# driver-power-stage.net
KiCad netlist of a schematic drawn in Altium Designer
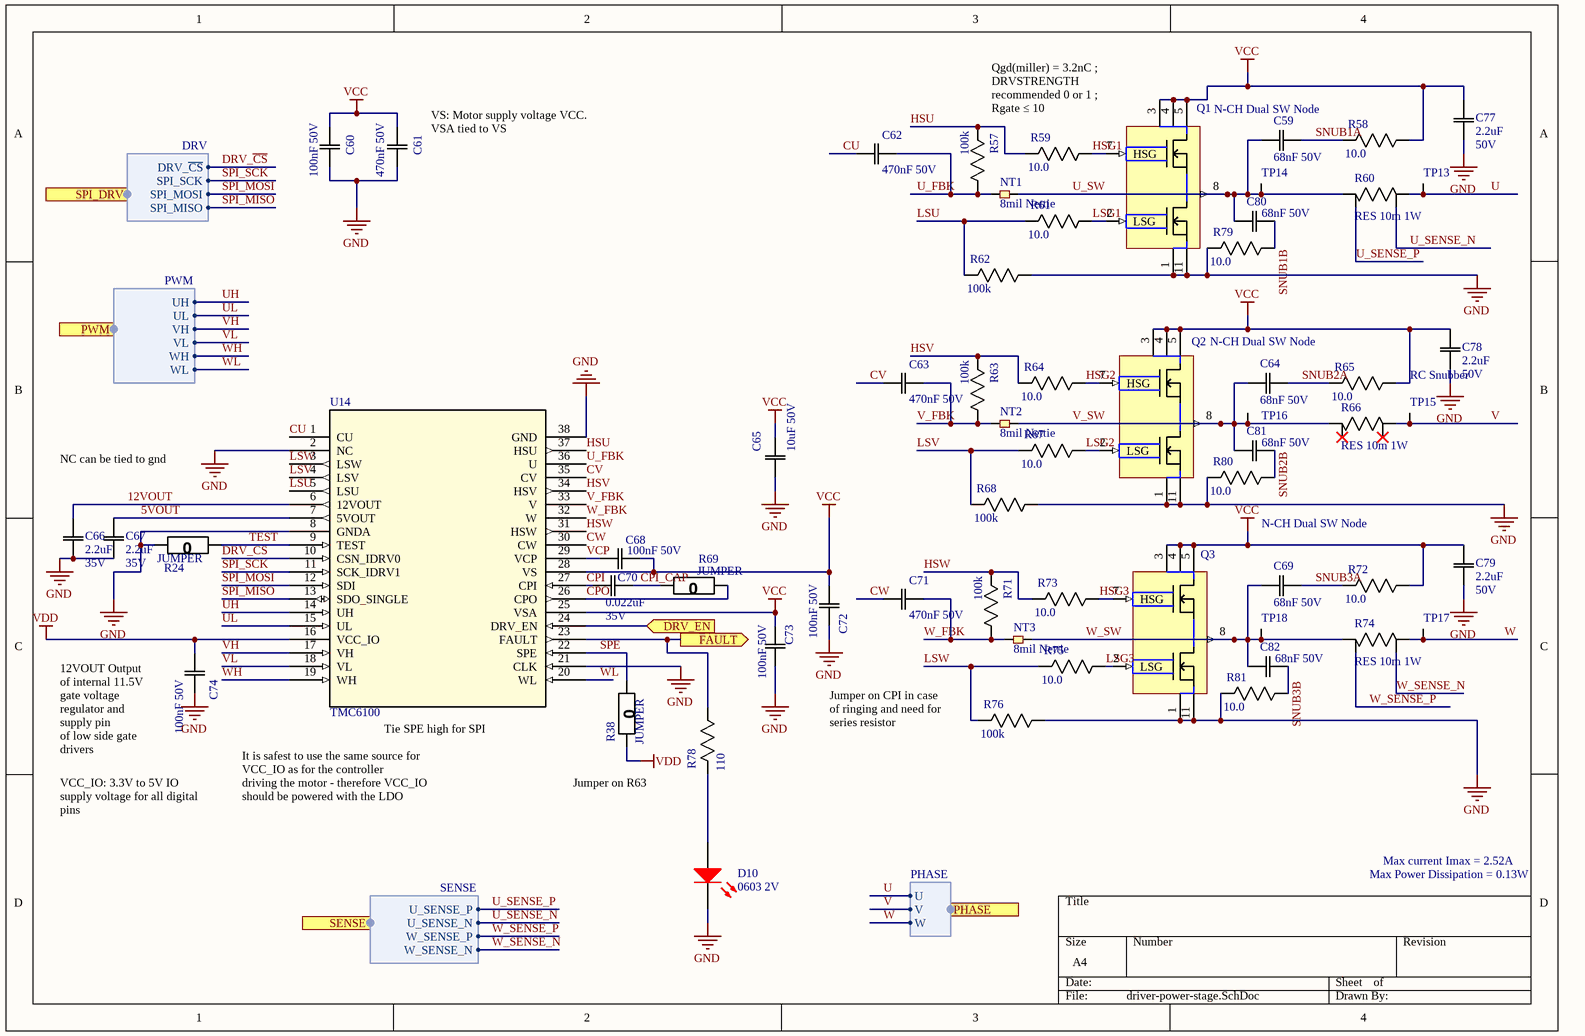
[diagram p0: driver-power-stage.SchDoc]

(export (version "E")
  (design (tool "Eeschema 10.0.6"))
  (components
    (comp (ref "C59")
      (value "68nF 50V")
      (footprint "0603")
      (description "Default Symbol for Capacitors")
      (fields (field (name "PART NUMBER") "CAP 0.068uF 50V") (field (name "TOLERANCE") "10%"))
      (libsource (lib "capacitor_library") (part "CAP_Default"))
    )
    (comp (ref "C60")
      (value "100nF 50V")
      (footprint "0603")
      (description "Default Symbol for Capacitors")
      (fields (field (name "TOLERANCE") "10%") (field (name "PART NUMBER") "CAP 100nF 50V"))
      (libsource (lib "capacitor_library") (part "CAP_Default"))
    )
    (comp (ref "C61")
      (value "470nF 50V")
      (footprint "0603")
      (description "Default Symbol for Capacitors")
      (fields (field (name "TOLERANCE") "10%") (field (name "PART NUMBER") "CAP 470nF 50V"))
      (libsource (lib "capacitor_library") (part "CAP_Default"))
    )
    (comp (ref "C62")
      (value "470nF 50V")
      (footprint "0603")
      (description "Default Symbol for Capacitors")
      (fields (field (name "TOLERANCE") "10%") (field (name "PART NUMBER") "CAP 470nF 50V"))
      (libsource (lib "capacitor_library") (part "CAP_Default"))
    )
    (comp (ref "C63")
      (value "470nF 50V")
      (footprint "0603")
      (description "Default Symbol for Capacitors")
      (fields (field (name "TOLERANCE") "10%") (field (name "PART NUMBER") "CAP 470nF 50V"))
      (libsource (lib "capacitor_library") (part "CAP_Default"))
    )
    (comp (ref "C64")
      (value "68nF 50V")
      (footprint "0603")
      (description "Default Symbol for Capacitors")
      (fields (field (name "PART NUMBER") "CAP 0.068uF 50V") (field (name "TOLERANCE") "10%"))
      (libsource (lib "capacitor_library") (part "CAP_Default"))
    )
    (comp (ref "C65")
      (value "10uF 50V")
      (footprint "0805")
      (description "Default Symbol for Capacitors")
      (fields (field (name "TOLERANCE") "10%") (field (name "PART NUMBER") "CAP 10uF 50V"))
      (libsource (lib "capacitor_library") (part "CAP_Default"))
    )
    (comp (ref "C66")
      (value "2.2uF")
      (footprint "0603")
      (description "Default Symbol for Capacitors")
      (fields
        (field (name "TOLERANCE") "10%")
        (field (name "RATING") "35V")
        (field (name "PART NUMBER") "CAP 2.2uF 35V")
      )
      (libsource (lib "capacitor_library") (part "CAP_Default"))
    )
    (comp (ref "C67")
      (value "2.2uF")
      (footprint "0603")
      (description "Default Symbol for Capacitors")
      (fields
        (field (name "TOLERANCE") "10%")
        (field (name "RATING") "35V")
        (field (name "PART NUMBER") "CAP 2.2uF 35V")
      )
      (libsource (lib "capacitor_library") (part "CAP_Default"))
    )
    (comp (ref "C68")
      (value "100nF 50V")
      (footprint "0603")
      (description "Default Symbol for Capacitors")
      (fields (field (name "TOLERANCE") "10%") (field (name "PART NUMBER") "CAP 100nF 50V"))
      (libsource (lib "capacitor_library") (part "CAP_Default"))
    )
    (comp (ref "C69")
      (value "68nF 50V")
      (footprint "0603")
      (description "Default Symbol for Capacitors")
      (fields (field (name "PART NUMBER") "CAP 0.068uF 50V") (field (name "TOLERANCE") "10%"))
      (libsource (lib "capacitor_library") (part "CAP_Default"))
    )
    (comp (ref "C70")
      (value "0.022uF")
      (footprint "0603")
      (description "Default Symbol for Capacitors")
      (fields
        (field (name "TOLERANCE") "10%")
        (field (name "RATING") "35V")
        (field (name "PART NUMBER") "CAP 0.022uF 35V")
      )
      (libsource (lib "capacitor_library") (part "CAP_Default"))
    )
    (comp (ref "C71")
      (value "470nF 50V")
      (footprint "0603")
      (description "Default Symbol for Capacitors")
      (fields (field (name "TOLERANCE") "10%") (field (name "PART NUMBER") "CAP 470nF 50V"))
      (libsource (lib "capacitor_library") (part "CAP_Default"))
    )
    (comp (ref "C72")
      (value "100nF 50V")
      (footprint "0603")
      (description "Default Symbol for Capacitors")
      (fields (field (name "TOLERANCE") "10%") (field (name "PART NUMBER") "CAP 100nF 50V"))
      (libsource (lib "capacitor_library") (part "CAP_Default"))
    )
    (comp (ref "C73")
      (value "100nF 50V")
      (footprint "0603")
      (description "Default Symbol for Capacitors")
      (fields (field (name "TOLERANCE") "10%") (field (name "PART NUMBER") "CAP 100nF 50V"))
      (libsource (lib "capacitor_library") (part "CAP_Default"))
    )
    (comp (ref "C74")
      (value "100nF 50V")
      (footprint "0603")
      (description "Default Symbol for Capacitors")
      (fields (field (name "TOLERANCE") "10%") (field (name "PART NUMBER") "CAP 100nF 50V"))
      (libsource (lib "capacitor_library") (part "CAP_Default"))
    )
    (comp (ref "C77")
      (value "2.2uF")
      (footprint "0603")
      (description "CAP CER 2.2UF 50V X5R 0603/0805")
      (fields
        (field (name "TOLERANCE") "10%")
        (field (name "RATING") "50V")
        (field (name "PART NUMBER") "CAP 2.2uF 50V")
      )
      (libsource (lib "capacitor_library") (part "CAP 2.2uF 50V"))
    )
    (comp (ref "C78")
      (value "2.2uF")
      (footprint "0603")
      (description "CAP CER 2.2UF 50V X5R 0603/0805")
      (fields
        (field (name "TOLERANCE") "10%")
        (field (name "RATING") "50V")
        (field (name "PART NUMBER") "CAP 2.2uF 50V")
      )
      (libsource (lib "capacitor_library") (part "CAP 2.2uF 50V"))
    )
    (comp (ref "C79")
      (value "2.2uF")
      (footprint "0603")
      (description "CAP CER 2.2UF 50V X5R 0603/0805")
      (fields
        (field (name "TOLERANCE") "10%")
        (field (name "RATING") "50V")
        (field (name "PART NUMBER") "CAP 2.2uF 50V")
      )
      (libsource (lib "capacitor_library") (part "CAP 2.2uF 50V"))
    )
    (comp (ref "C80")
      (value "68nF 50V")
      (footprint "0603")
      (description "Default Symbol for Capacitors")
      (fields (field (name "PART NUMBER") "CAP 0.068uF 50V") (field (name "TOLERANCE") "10%"))
      (libsource (lib "capacitor_library") (part "CAP_Default"))
    )
    (comp (ref "C81")
      (value "68nF 50V")
      (footprint "0603")
      (description "Default Symbol for Capacitors")
      (fields (field (name "PART NUMBER") "CAP 0.068uF 50V") (field (name "TOLERANCE") "10%"))
      (libsource (lib "capacitor_library") (part "CAP_Default"))
    )
    (comp (ref "C82")
      (value "68nF 50V")
      (footprint "0603")
      (description "Default Symbol for Capacitors")
      (fields (field (name "PART NUMBER") "CAP 0.068uF 50V") (field (name "TOLERANCE") "10%"))
      (libsource (lib "capacitor_library") (part "CAP_Default"))
    )
    (comp (ref "D10")
      (value "0603 2V")
      (footprint "0603 - LED2")
      (description "0603 red led alingap 631nm-639nm water clear 18-180mcd 130d")
      (fields (field (name "PART NUMBER") "LED RED SMD 0603"))
      (libsource (lib "Diode_Library") (part "LED RED SMD 0603"))
    )
    (comp (ref "NT1")
      (value "8mil Nettie")
      (footprint "NT_8mil")
      (description "8mil wide nettie")
      (fields (field (name "PART NUMBER") "NT_8"))
      (libsource (lib "Resistor_Library") (part "NT_8"))
    )
    (comp (ref "NT2")
      (value "8mil Nettie")
      (footprint "NT_8mil")
      (description "8mil wide nettie")
      (fields (field (name "PART NUMBER") "NT_8"))
      (libsource (lib "Resistor_Library") (part "NT_8"))
    )
    (comp (ref "NT3")
      (value "8mil Nettie")
      (footprint "NT_8mil")
      (description "8mil wide nettie")
      (fields (field (name "PART NUMBER") "NT_8"))
      (libsource (lib "Resistor_Library") (part "NT_8"))
    )
    (comp (ref "Q1")
      (value "N-CH Dual SW Node")
      (footprint "12-PowerWQFN")
      (description "MOSFET N+N COMMON PHASE SW 40V 60A")
      (fields (field (name "PART NUMBER") "MOSFET N-CH DUAL NTTFD4D0N04HLTWG"))
      (libsource (lib "Transistor_Library") (part "MOSFET N-CH DUAL NTTFD4D0N04HLTWG"))
    )
    (comp (ref "Q2")
      (value "N-CH Dual SW Node")
      (footprint "12-PowerWQFN")
      (description "MOSFET N+N COMMON PHASE SW 40V 60A")
      (fields (field (name "PART NUMBER") "MOSFET N-CH DUAL NTTFD4D0N04HLTWG"))
      (libsource (lib "Transistor_Library") (part "MOSFET N-CH DUAL NTTFD4D0N04HLTWG"))
    )
    (comp (ref "Q3")
      (value "N-CH Dual SW Node")
      (footprint "12-PowerWQFN")
      (description "MOSFET N+N COMMON PHASE SW 40V 60A")
      (fields (field (name "PART NUMBER") "MOSFET N-CH DUAL NTTFD4D0N04HLTWG"))
      (libsource (lib "Transistor_Library") (part "MOSFET N-CH DUAL NTTFD4D0N04HLTWG"))
    )
    (comp (ref "R24")
      (value "JUMPER")
      (footprint "0603")
      (description "RES SMD 0 OHM JUMPER GENERIC 0805")
      (fields (field (name "PART NUMBER") "RES 0 JUMPER"))
      (libsource (lib "Resistor_Library") (part "RES 0 JUMPER"))
    )
    (comp (ref "R38")
      (value "JUMPER")
      (footprint "0603")
      (description "RES SMD 0 OHM JUMPER GENERIC 0805")
      (fields (field (name "PART NUMBER") "RES 0 JUMPER"))
      (libsource (lib "Resistor_Library") (part "RES 0 JUMPER"))
    )
    (comp (ref "R57")
      (value "100k")
      (footprint "0603")
      (description "RES SMD 100K OHM 5% 1/8W 0805")
      (fields (field (name "TOLERANCE") "5%") (field (name "PART NUMBER") "RES 100k 1/8W 5%"))
      (libsource (lib "Resistor_Library") (part "RES_DEFAULT"))
    )
    (comp (ref "R58")
      (value "10.0")
      (footprint "0603")
      (description "Default Resistor Symbol")
      (fields (field (name "TOLERANCE") "1%") (field (name "PART NUMBER") "RES 10.0 1/8W - 1%"))
      (libsource (lib "") (part "RES_DEFAULT_1"))
    )
    (comp (ref "R59")
      (value "10.0")
      (footprint "0603")
      (description "Default Resistor Symbol")
      (fields (field (name "TOLERANCE") "1%") (field (name "PART NUMBER") "RES 10.0 1/8W - 1%"))
      (libsource (lib "Resistor_Library") (part "RES_DEFAULT"))
    )
    (comp (ref "R60")
      (value "RES 10m 1W")
      (footprint "1206 - Current Sense")
      (description "RES SMD 0.01 OHM 1% 1W 1206")
      (fields (field (name "TOLERANCE") "1%"))
      (libsource (lib "Resistor_Library") (part "RES 10m 1W"))
    )
    (comp (ref "R61")
      (value "10.0")
      (footprint "0603")
      (description "Default Resistor Symbol")
      (fields (field (name "TOLERANCE") "1%") (field (name "PART NUMBER") "RES 10.0 1/8W - 1%"))
      (libsource (lib "Resistor_Library") (part "RES_DEFAULT"))
    )
    (comp (ref "R62")
      (value "100k")
      (footprint "0603")
      (description "RES SMD 100K OHM 5% 1/8W 0805")
      (fields (field (name "TOLERANCE") "5%") (field (name "PART NUMBER") "RES 100k 1/8W 5%"))
      (libsource (lib "Resistor_Library") (part "RES_DEFAULT"))
    )
    (comp (ref "R63")
      (value "100k")
      (footprint "0603")
      (description "RES SMD 100K OHM 5% 1/8W 0805")
      (fields (field (name "TOLERANCE") "5%") (field (name "PART NUMBER") "RES 100k 1/8W 5%"))
      (libsource (lib "Resistor_Library") (part "RES_DEFAULT"))
    )
    (comp (ref "R64")
      (value "10.0")
      (footprint "0603")
      (description "Default Resistor Symbol")
      (fields (field (name "TOLERANCE") "1%") (field (name "PART NUMBER") "RES 10.0 1/8W - 1%"))
      (libsource (lib "") (part "RES_DEFAULT_1"))
    )
    (comp (ref "R65")
      (value "10.0")
      (footprint "0603")
      (description "Default Resistor Symbol")
      (fields (field (name "TOLERANCE") "1%") (field (name "PART NUMBER") "RES 10.0 1/8W - 1%"))
      (libsource (lib "") (part "RES_DEFAULT_1"))
    )
    (comp (ref "R66")
      (value "RES 10m 1W")
      (footprint "1206 - Current Sense")
      (description "RES SMD 0.01 OHM 1% 1W 1206")
      (fields (field (name "TOLERANCE") "1%"))
      (libsource (lib "Resistor_Library") (part "RES 10m 1W"))
    )
    (comp (ref "R67")
      (value "10.0")
      (footprint "0603")
      (description "Default Resistor Symbol")
      (fields (field (name "TOLERANCE") "1%") (field (name "PART NUMBER") "RES 10.0 1/8W - 1%"))
      (libsource (lib "Resistor_Library") (part "RES_DEFAULT"))
    )
    (comp (ref "R68")
      (value "100k")
      (footprint "0603")
      (description "RES SMD 100K OHM 5% 1/8W 0805")
      (fields (field (name "TOLERANCE") "5%") (field (name "PART NUMBER") "RES 100k 1/8W 5%"))
      (libsource (lib "Resistor_Library") (part "RES_DEFAULT"))
    )
    (comp (ref "R69")
      (value "JUMPER")
      (footprint "0603")
      (description "RES SMD 0 OHM JUMPER GENERIC 0805")
      (fields (field (name "PART NUMBER") "RES 0 JUMPER"))
      (libsource (lib "Resistor_Library") (part "RES 0 JUMPER"))
    )
    (comp (ref "R71")
      (value "100k")
      (footprint "0603")
      (description "RES SMD 100K OHM 5% 1/8W 0805")
      (fields (field (name "TOLERANCE") "5%") (field (name "PART NUMBER") "RES 100k 1/8W 5%"))
      (libsource (lib "Resistor_Library") (part "RES_DEFAULT"))
    )
    (comp (ref "R72")
      (value "10.0")
      (footprint "0603")
      (description "Default Resistor Symbol")
      (fields (field (name "TOLERANCE") "1%") (field (name "PART NUMBER") "RES 10.0 1/8W - 1%"))
      (libsource (lib "") (part "RES_DEFAULT_1"))
    )
    (comp (ref "R73")
      (value "10.0")
      (footprint "0603")
      (description "Default Resistor Symbol")
      (fields (field (name "TOLERANCE") "1%") (field (name "PART NUMBER") "RES 10.0 1/8W - 1%"))
      (libsource (lib "") (part "RES_DEFAULT_1"))
    )
    (comp (ref "R74")
      (value "RES 10m 1W")
      (footprint "1206 - Current Sense")
      (description "RES SMD 0.01 OHM 1% 1W 1206")
      (fields (field (name "TOLERANCE") "1%"))
      (libsource (lib "Resistor_Library") (part "RES 10m 1W"))
    )
    (comp (ref "R75")
      (value "10.0")
      (footprint "0603")
      (description "Default Resistor Symbol")
      (fields (field (name "TOLERANCE") "1%") (field (name "PART NUMBER") "RES 10.0 1/8W - 1%"))
      (libsource (lib "") (part "RES_DEFAULT_1"))
    )
    (comp (ref "R76")
      (value "100k")
      (footprint "0603")
      (description "RES SMD 100K OHM 5% 1/8W 0805")
      (fields (field (name "TOLERANCE") "5%") (field (name "PART NUMBER") "RES 100k 1/8W 5%"))
      (libsource (lib "Resistor_Library") (part "RES_DEFAULT"))
    )
    (comp (ref "R78")
      (value "110")
      (footprint "0603")
      (description "Default Resistor Symbol")
      (fields (field (name "TOLERANCE") "1%") (field (name "PART NUMBER") "RES 110.0 1/8W - 1%"))
      (libsource (lib "Resistor_Library") (part "RES_DEFAULT"))
    )
    (comp (ref "R79")
      (value "10.0")
      (footprint "0603")
      (description "Default Resistor Symbol")
      (fields (field (name "TOLERANCE") "1%") (field (name "PART NUMBER") "RES 10.0 1/8W - 1%"))
      (libsource (lib "Resistor_Library") (part "RES_DEFAULT"))
    )
    (comp (ref "R80")
      (value "10.0")
      (footprint "0603")
      (description "Default Resistor Symbol")
      (fields (field (name "TOLERANCE") "1%") (field (name "PART NUMBER") "RES 10.0 1/8W - 1%"))
      (libsource (lib "Resistor_Library") (part "RES_DEFAULT"))
    )
    (comp (ref "R81")
      (value "10.0")
      (footprint "0603")
      (description "Default Resistor Symbol")
      (fields (field (name "TOLERANCE") "1%") (field (name "PART NUMBER") "RES 10.0 1/8W - 1%"))
      (libsource (lib "Resistor_Library") (part "RES_DEFAULT"))
    )
    (comp (ref "TP13")
      (value "U_SL")
      (footprint "TP")
      (fields (field (name "PART NUMBER") "Test Point (Via)"))
      (libsource (lib "IC_Library") (part "Test Point (Via)"))
    )
    (comp (ref "TP14")
      (value "U_SH")
      (footprint "TP")
      (fields (field (name "PART NUMBER") "Test Point (Via)"))
      (libsource (lib "IC_Library") (part "Test Point (Via)"))
    )
    (comp (ref "TP15")
      (value "V_SL")
      (footprint "TP")
      (fields (field (name "PART NUMBER") "Test Point (Via)"))
      (libsource (lib "IC_Library") (part "Test Point (Via)"))
    )
    (comp (ref "TP16")
      (value "V_SH")
      (footprint "TP")
      (fields (field (name "PART NUMBER") "Test Point (Via)"))
      (libsource (lib "IC_Library") (part "Test Point (Via)"))
    )
    (comp (ref "TP17")
      (value "W_SL")
      (footprint "TP")
      (fields (field (name "PART NUMBER") "Test Point (Via)"))
      (libsource (lib "IC_Library") (part "Test Point (Via)"))
    )
    (comp (ref "TP18")
      (value "W_SH")
      (footprint "TP")
      (fields (field (name "PART NUMBER") "Test Point (Via)"))
      (libsource (lib "IC_Library") (part "Test Point (Via)"))
    )
    (comp (ref "U14")
      (value "TMC6100")
      (footprint "QFN50P700X700X85_HS-38N")
      (description "GATE DRIVER IC 8-60V QFN37")
      (libsource (lib "IC_Library") (part "TMC6100"))
    )
  )
  (nets
    (net (code "5") (name "/5VOUT") (class "Default")
      (node (ref "C67") (pin "2") (pinfunction "C2_2") (pintype "passive"))
      (node (ref "U14") (pin "7") (pinfunction "5VOUT_7") (pintype "output"))
    )
    (net (code "6") (name "/12VOUT") (class "Default")
      (node (ref "C66") (pin "2") (pinfunction "C2_2") (pintype "passive"))
      (node (ref "U14") (pin "6") (pinfunction "12VOUT_6") (pintype "output"))
    )
    (net (code "7") (name "/CPI") (class "Default")
      (node (ref "C70") (pin "1") (pinfunction "C1_1") (pintype "passive"))
      (node (ref "U14") (pin "27") (pinfunction "CPI_27") (pintype "input"))
    )
    (net (code "8") (name "/CPI_CAP") (class "Default")
      (node (ref "C70") (pin "2") (pinfunction "C2_2") (pintype "passive"))
      (node (ref "R69") (pin "2") (pinfunction "R2_2") (pintype "passive"))
    )
    (net (code "9") (name "/CPO") (class "Default")
      (node (ref "R69") (pin "1") (pinfunction "R1_1") (pintype "passive"))
      (node (ref "U14") (pin "26") (pinfunction "CPO_26") (pintype "output"))
    )
    (net (code "10") (name "/CU") (class "Default")
      (node (ref "C62") (pin "1") (pinfunction "C1_1") (pintype "passive"))
      (node (ref "U14") (pin "1") (pinfunction "CU_1") (pintype "passive"))
    )
    (net (code "11") (name "/CV") (class "Default")
      (node (ref "C63") (pin "1") (pinfunction "C1_1") (pintype "passive"))
      (node (ref "U14") (pin "35") (pinfunction "CV_35") (pintype "passive"))
    )
    (net (code "12") (name "/CW") (class "Default")
      (node (ref "C71") (pin "1") (pinfunction "C1_1") (pintype "passive"))
      (node (ref "U14") (pin "30") (pinfunction "CW_30") (pintype "passive"))
    )
    (net (code "13") (name "/DRV_EN") (class "Default")
      (node (ref "U14") (pin "24") (pinfunction "DRV_EN_24") (pintype "input"))
    )
    (net (code "14") (name "/DRV_~{CS}") (class "Default")
      (node (ref "U14") (pin "10") (pinfunction "CSN_IDRV0_10") (pintype "input"))
    )
    (net (code "15") (name "/FAULT") (class "Default")
      (node (ref "R78") (pin "1") (pinfunction "R1_1") (pintype "passive"))
      (node (ref "U14") (pin "23") (pinfunction "FAULT_23") (pintype "output"))
    )
    (net (code "16") (name "/HSG1") (class "Default")
      (node (ref "Q1") (pin "7") (pinfunction "HSG_7") (pintype "input"))
      (node (ref "R59") (pin "1") (pinfunction "R1_1") (pintype "passive"))
    )
    (net (code "17") (name "/HSG2") (class "Default")
      (node (ref "Q2") (pin "7") (pinfunction "HSG_7") (pintype "input"))
      (node (ref "R64") (pin "1") (pinfunction "R1_1") (pintype "passive"))
    )
    (net (code "18") (name "/HSG3") (class "Default")
      (node (ref "Q3") (pin "7") (pinfunction "HSG_7") (pintype "input"))
      (node (ref "R73") (pin "1") (pinfunction "R1_1") (pintype "passive"))
    )
    (net (code "19") (name "/HSU") (class "Default")
      (node (ref "R57") (pin "2") (pinfunction "R2_2") (pintype "passive"))
      (node (ref "R59") (pin "2") (pinfunction "R2_2") (pintype "passive"))
      (node (ref "U14") (pin "37") (pinfunction "HSU_37") (pintype "output"))
    )
    (net (code "20") (name "/HSV") (class "Default")
      (node (ref "R63") (pin "2") (pinfunction "R2_2") (pintype "passive"))
      (node (ref "R64") (pin "2") (pinfunction "R2_2") (pintype "passive"))
      (node (ref "U14") (pin "34") (pinfunction "HSV_34") (pintype "output"))
    )
    (net (code "21") (name "/HSW") (class "Default")
      (node (ref "R71") (pin "2") (pinfunction "R2_2") (pintype "passive"))
      (node (ref "R73") (pin "2") (pinfunction "R2_2") (pintype "passive"))
      (node (ref "U14") (pin "31") (pinfunction "HSW_31") (pintype "output"))
    )
    (net (code "22") (name "/LSG1") (class "Default")
      (node (ref "Q1") (pin "2") (pinfunction "LSG_2") (pintype "input"))
      (node (ref "R61") (pin "1") (pinfunction "R1_1") (pintype "passive"))
    )
    (net (code "23") (name "/LSG2") (class "Default")
      (node (ref "Q2") (pin "2") (pinfunction "LSG_2") (pintype "input"))
      (node (ref "R67") (pin "1") (pinfunction "R1_1") (pintype "passive"))
    )
    (net (code "24") (name "/LSG3") (class "Default")
      (node (ref "Q3") (pin "2") (pinfunction "LSG_2") (pintype "input"))
      (node (ref "R75") (pin "1") (pinfunction "R1_1") (pintype "passive"))
    )
    (net (code "25") (name "/LSU") (class "Default")
      (node (ref "R61") (pin "2") (pinfunction "R2_2") (pintype "passive"))
      (node (ref "R62") (pin "2") (pinfunction "R2_2") (pintype "passive"))
      (node (ref "U14") (pin "5") (pinfunction "LSU_5") (pintype "output"))
    )
    (net (code "26") (name "/LSV") (class "Default")
      (node (ref "R67") (pin "2") (pinfunction "R2_2") (pintype "passive"))
      (node (ref "R68") (pin "2") (pinfunction "R2_2") (pintype "passive"))
      (node (ref "U14") (pin "4") (pinfunction "LSV_4") (pintype "output"))
    )
    (net (code "27") (name "/LSW") (class "Default")
      (node (ref "R75") (pin "2") (pinfunction "R2_2") (pintype "passive"))
      (node (ref "R76") (pin "2") (pinfunction "R2_2") (pintype "passive"))
      (node (ref "U14") (pin "3") (pinfunction "LSW_3") (pintype "output"))
    )
    (net (code "28") (name "/SNUB1A") (class "Default")
      (node (ref "C59") (pin "2") (pinfunction "C2_2") (pintype "passive"))
      (node (ref "R58") (pin "2") (pinfunction "R2_2") (pintype "passive"))
    )
    (net (code "29") (name "/SNUB1B") (class "Default")
      (node (ref "C80") (pin "2") (pinfunction "C2_2") (pintype "passive"))
      (node (ref "R79") (pin "1") (pinfunction "R1_1") (pintype "passive"))
    )
    (net (code "30") (name "/SNUB2A") (class "Default")
      (node (ref "C64") (pin "2") (pinfunction "C2_2") (pintype "passive"))
      (node (ref "R65") (pin "2") (pinfunction "R2_2") (pintype "passive"))
    )
    (net (code "31") (name "/SNUB2B") (class "Default")
      (node (ref "C81") (pin "2") (pinfunction "C2_2") (pintype "passive"))
      (node (ref "R80") (pin "1") (pinfunction "R1_1") (pintype "passive"))
    )
    (net (code "32") (name "/SNUB3A") (class "Default")
      (node (ref "C69") (pin "2") (pinfunction "C2_2") (pintype "passive"))
      (node (ref "R72") (pin "2") (pinfunction "R2_2") (pintype "passive"))
    )
    (net (code "33") (name "/SNUB3B") (class "Default")
      (node (ref "C82") (pin "2") (pinfunction "C2_2") (pintype "passive"))
      (node (ref "R81") (pin "1") (pinfunction "R1_1") (pintype "passive"))
    )
    (net (code "34") (name "/SPE") (class "Default")
      (node (ref "R38") (pin "1") (pinfunction "R1_1") (pintype "passive"))
      (node (ref "U14") (pin "22") (pinfunction "SPE_22") (pintype "input"))
    )
    (net (code "35") (name "/SPI_MISO") (class "Default")
      (node (ref "U14") (pin "13") (pinfunction "SDO_SINGLE_13") (pintype "bidirectional"))
    )
    (net (code "36") (name "/SPI_MOSI") (class "Default")
      (node (ref "U14") (pin "12") (pinfunction "SDI_12") (pintype "input"))
    )
    (net (code "37") (name "/SPI_SCK") (class "Default")
      (node (ref "U14") (pin "11") (pinfunction "SCK_IDRV1_11") (pintype "input"))
    )
    (net (code "38") (name "/TEST") (class "Default")
      (node (ref "R24") (pin "1") (pinfunction "R1_1") (pintype "passive"))
      (node (ref "U14") (pin "9") (pinfunction "TEST_9") (pintype "input"))
    )
    (net (code "39") (name "/U") (class "Default")
      (node (ref "R60") (pin "1") (pinfunction "1_1") (pintype "passive"))
      (node (ref "TP13") (pin "1") (pinfunction "1_1") (pintype "passive"))
    )
    (net (code "40") (name "/UH") (class "Default")
      (node (ref "U14") (pin "14") (pinfunction "UH_14") (pintype "input"))
    )
    (net (code "41") (name "/UL") (class "Default")
      (node (ref "U14") (pin "15") (pinfunction "UL_15") (pintype "input"))
    )
    (net (code "42") (name "/U_FBK") (class "Default")
      (node (ref "C62") (pin "2") (pinfunction "C2_2") (pintype "passive"))
      (node (ref "NT1") (pin "1") (pinfunction "1_1") (pintype "passive"))
      (node (ref "R57") (pin "1") (pinfunction "R1_1") (pintype "passive"))
      (node (ref "U14") (pin "36") (pinfunction "U_36") (pintype "passive"))
    )
    (net (code "43") (name "/U_SENSE_N") (class "Default")
      (node (ref "R60") (pin "S1") (pinfunction "S1_S1") (pintype "passive"))
    )
    (net (code "44") (name "/U_SENSE_P") (class "Default")
      (node (ref "R60") (pin "S2") (pinfunction "S2_S2") (pintype "passive"))
    )
    (net (code "45") (name "/U_SW") (class "Default")
      (node (ref "C59") (pin "1") (pinfunction "C1_1") (pintype "passive"))
      (node (ref "C80") (pin "1") (pinfunction "C1_1") (pintype "passive"))
      (node (ref "NT1") (pin "2") (pinfunction "2_2") (pintype "passive"))
      (node (ref "Q1") (pin "8") (pinfunction "SW_8") (pintype "output"))
      (node (ref "R60") (pin "2") (pinfunction "2_2") (pintype "passive"))
      (node (ref "TP14") (pin "1") (pinfunction "1_1") (pintype "passive"))
    )
    (net (code "46") (name "/V") (class "Default")
      (node (ref "R66") (pin "1") (pinfunction "1_1") (pintype "passive"))
      (node (ref "TP15") (pin "1") (pinfunction "1_1") (pintype "passive"))
    )
    (net (code "47") (name "/VCP") (class "Default")
      (node (ref "C68") (pin "1") (pinfunction "C1_1") (pintype "passive"))
      (node (ref "U14") (pin "29") (pinfunction "VCP_29") (pintype "power_in"))
    )
    (net (code "48") (name "/VH") (class "Default")
      (node (ref "U14") (pin "17") (pinfunction "VH_17") (pintype "input"))
    )
    (net (code "49") (name "/VL") (class "Default")
      (node (ref "U14") (pin "18") (pinfunction "VL_18") (pintype "input"))
    )
    (net (code "50") (name "/V_FBK") (class "Default")
      (node (ref "C63") (pin "2") (pinfunction "C2_2") (pintype "passive"))
      (node (ref "NT2") (pin "1") (pinfunction "1_1") (pintype "passive"))
      (node (ref "R63") (pin "1") (pinfunction "R1_1") (pintype "passive"))
      (node (ref "U14") (pin "33") (pinfunction "V_33") (pintype "passive"))
    )
    (net (code "51") (name "/V_SW") (class "Default")
      (node (ref "C64") (pin "1") (pinfunction "C1_1") (pintype "passive"))
      (node (ref "C81") (pin "1") (pinfunction "C1_1") (pintype "passive"))
      (node (ref "NT2") (pin "2") (pinfunction "2_2") (pintype "passive"))
      (node (ref "Q2") (pin "8") (pinfunction "SW_8") (pintype "output"))
      (node (ref "R66") (pin "2") (pinfunction "2_2") (pintype "passive"))
      (node (ref "TP16") (pin "1") (pinfunction "1_1") (pintype "passive"))
    )
    (net (code "52") (name "/W") (class "Default")
      (node (ref "R74") (pin "1") (pinfunction "1_1") (pintype "passive"))
      (node (ref "TP17") (pin "1") (pinfunction "1_1") (pintype "passive"))
    )
    (net (code "53") (name "/WH") (class "Default")
      (node (ref "U14") (pin "19") (pinfunction "WH_19") (pintype "input"))
    )
    (net (code "54") (name "/WL") (class "Default")
      (node (ref "U14") (pin "20") (pinfunction "WL_20") (pintype "input"))
    )
    (net (code "55") (name "/W_FBK") (class "Default")
      (node (ref "C71") (pin "2") (pinfunction "C2_2") (pintype "passive"))
      (node (ref "NT3") (pin "1") (pinfunction "1_1") (pintype "passive"))
      (node (ref "R71") (pin "1") (pinfunction "R1_1") (pintype "passive"))
      (node (ref "U14") (pin "32") (pinfunction "W_32") (pintype "passive"))
    )
    (net (code "56") (name "/W_SENSE_N") (class "Default")
      (node (ref "R74") (pin "S1") (pinfunction "S1_S1") (pintype "passive"))
    )
    (net (code "57") (name "/W_SENSE_P") (class "Default")
      (node (ref "R74") (pin "S2") (pinfunction "S2_S2") (pintype "passive"))
    )
    (net (code "58") (name "/W_SW") (class "Default")
      (node (ref "C69") (pin "1") (pinfunction "C1_1") (pintype "passive"))
      (node (ref "C82") (pin "1") (pinfunction "C1_1") (pintype "passive"))
      (node (ref "NT3") (pin "2") (pinfunction "2_2") (pintype "passive"))
      (node (ref "Q3") (pin "8") (pinfunction "SW_8") (pintype "output"))
      (node (ref "R74") (pin "2") (pinfunction "2_2") (pintype "passive"))
      (node (ref "TP18") (pin "1") (pinfunction "1_1") (pintype "passive"))
    )
    (net (code "63") (name "GND") (class "Default")
      (node (ref "C60") (pin "2") (pinfunction "C2_2") (pintype "passive"))
      (node (ref "C61") (pin "2") (pinfunction "C2_2") (pintype "passive"))
      (node (ref "C65") (pin "1") (pinfunction "C1_1") (pintype "passive"))
      (node (ref "C66") (pin "1") (pinfunction "C1_1") (pintype "passive"))
      (node (ref "C67") (pin "1") (pinfunction "C1_1") (pintype "passive"))
      (node (ref "C72") (pin "2") (pinfunction "C2_2") (pintype "passive"))
      (node (ref "C73") (pin "2") (pinfunction "C2_2") (pintype "passive"))
      (node (ref "C74") (pin "2") (pinfunction "C2_2") (pintype "passive"))
      (node (ref "C77") (pin "1") (pinfunction "C1_1") (pintype "passive"))
      (node (ref "C78") (pin "1") (pinfunction "C1_1") (pintype "passive"))
      (node (ref "C79") (pin "1") (pinfunction "C1_1") (pintype "passive"))
      (node (ref "D10") (pin "2") (pinfunction "K_2") (pintype "passive"))
      (node (ref "Q1") (pin "1") (pinfunction "GND_1") (pintype "power_in"))
      (node (ref "Q1") (pin "11") (pinfunction "GND_11") (pintype "power_in"))
      (node (ref "Q2") (pin "1") (pinfunction "GND_1") (pintype "power_in"))
      (node (ref "Q2") (pin "11") (pinfunction "GND_11") (pintype "power_in"))
      (node (ref "Q3") (pin "1") (pinfunction "GND_1") (pintype "power_in"))
      (node (ref "Q3") (pin "11") (pinfunction "GND_11") (pintype "power_in"))
      (node (ref "R24") (pin "2") (pinfunction "R2_2") (pintype "passive"))
      (node (ref "R62") (pin "1") (pinfunction "R1_1") (pintype "passive"))
      (node (ref "R68") (pin "1") (pinfunction "R1_1") (pintype "passive"))
      (node (ref "R76") (pin "1") (pinfunction "R1_1") (pintype "passive"))
      (node (ref "R79") (pin "2") (pinfunction "R2_2") (pintype "passive"))
      (node (ref "R80") (pin "2") (pinfunction "R2_2") (pintype "passive"))
      (node (ref "R81") (pin "2") (pinfunction "R2_2") (pintype "passive"))
      (node (ref "U14") (pin "2") (pinfunction "NC_2") (pintype "passive"))
      (node (ref "U14") (pin "21") (pinfunction "CLK_21") (pintype "input"))
      (node (ref "U14") (pin "38") (pinfunction "GND_38") (pintype "passive"))
      (node (ref "U14") (pin "8") (pinfunction "GNDA_8") (pintype "power_in"))
    )
    (net (code "64") (name "Net-(D10-A)") (class "Default")
      (node (ref "D10") (pin "1") (pinfunction "A_1") (pintype "passive"))
      (node (ref "R78") (pin "2") (pinfunction "R2_2") (pintype "passive"))
    )
    (net (code "65") (name "VCC") (class "Default")
      (node (ref "C60") (pin "1") (pinfunction "C1_1") (pintype "passive"))
      (node (ref "C61") (pin "1") (pinfunction "C1_1") (pintype "passive"))
      (node (ref "C65") (pin "2") (pinfunction "C2_2") (pintype "passive"))
      (node (ref "C68") (pin "2") (pinfunction "C2_2") (pintype "passive"))
      (node (ref "C72") (pin "1") (pinfunction "C1_1") (pintype "passive"))
      (node (ref "C73") (pin "1") (pinfunction "C1_1") (pintype "passive"))
      (node (ref "C77") (pin "2") (pinfunction "C2_2") (pintype "passive"))
      (node (ref "C78") (pin "2") (pinfunction "C2_2") (pintype "passive"))
      (node (ref "C79") (pin "2") (pinfunction "C2_2") (pintype "passive"))
      (node (ref "Q1") (pin "3") (pinfunction "V+_3") (pintype "power_in"))
      (node (ref "Q1") (pin "4") (pinfunction "V+_4") (pintype "power_in"))
      (node (ref "Q1") (pin "5") (pinfunction "V+_5") (pintype "power_in"))
      (node (ref "Q2") (pin "3") (pinfunction "V+_3") (pintype "power_in"))
      (node (ref "Q2") (pin "4") (pinfunction "V+_4") (pintype "power_in"))
      (node (ref "Q2") (pin "5") (pinfunction "V+_5") (pintype "power_in"))
      (node (ref "Q3") (pin "3") (pinfunction "V+_3") (pintype "power_in"))
      (node (ref "Q3") (pin "4") (pinfunction "V+_4") (pintype "power_in"))
      (node (ref "Q3") (pin "5") (pinfunction "V+_5") (pintype "power_in"))
      (node (ref "R58") (pin "1") (pinfunction "R1_1") (pintype "passive"))
      (node (ref "R65") (pin "1") (pinfunction "R1_1") (pintype "passive"))
      (node (ref "R72") (pin "1") (pinfunction "R1_1") (pintype "passive"))
      (node (ref "U14") (pin "25") (pinfunction "VSA_25") (pintype "power_in"))
      (node (ref "U14") (pin "28") (pinfunction "VS_28") (pintype "power_in"))
    )
    (net (code "66") (name "VDD") (class "Default")
      (node (ref "C74") (pin "1") (pinfunction "C1_1") (pintype "passive"))
      (node (ref "R38") (pin "2") (pinfunction "R2_2") (pintype "passive"))
      (node (ref "U14") (pin "16") (pinfunction "VCC_IO_16") (pintype "power_in"))
    )
    (net (code "67") (name "unconnected-(R66-PadS1)") (class "Default")
      (node (ref "R66") (pin "S1") (pinfunction "S1_S1") (pintype "passive+no_connect"))
    )
    (net (code "68") (name "unconnected-(R66-PadS2)") (class "Default")
      (node (ref "R66") (pin "S2") (pinfunction "S2_S2") (pintype "passive+no_connect"))
    )
  )
)
